# 4_-MECH_BUTTONS.net
KiCad netlist of a schematic drawn in Altium Designer
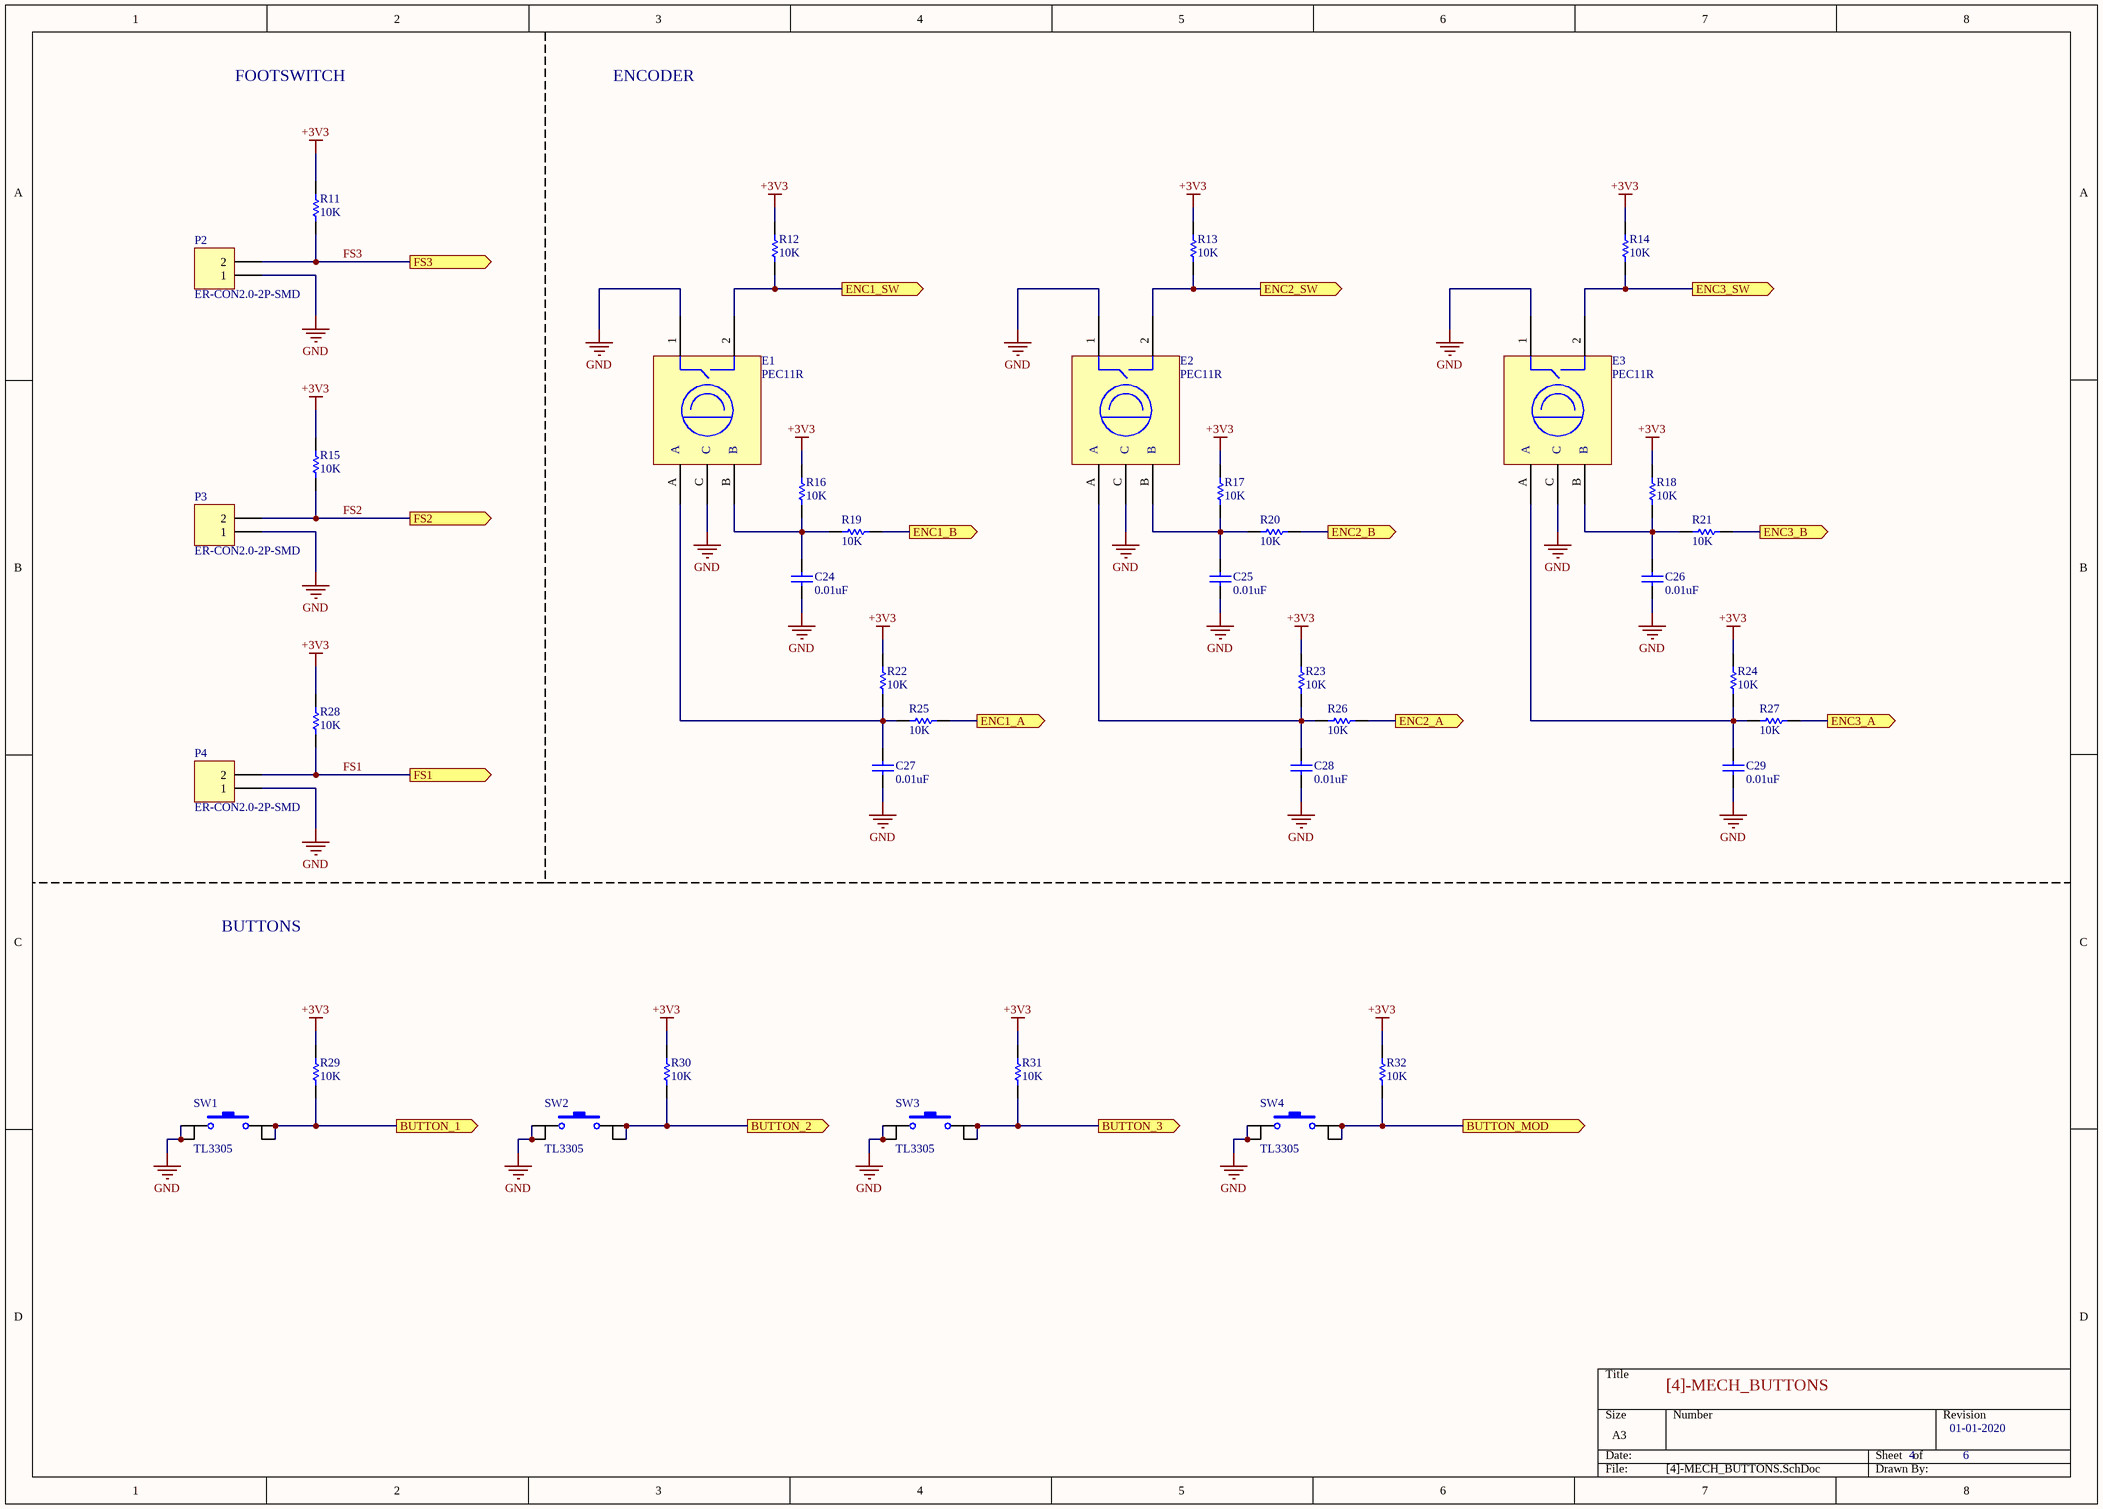
[diagram p0: [4]-MECH_BUTTONS.SchDoc]

(export (version "E")
  (design (tool "Eeschema 10.0.6"))
  (components
    (comp (ref "C24")
      (value "0.01uF")
      (footprint "CAPC1608N")
      (description "CAP CER 10000PF 50V X7R 0603")
      (fields (field (name "TOLERANCE") "10%") (field (name "VOLTAGE") "50V"))
      (libsource (lib "bitsnio") (part "06035C-103KAT2A"))
    )
    (comp (ref "C25")
      (value "0.01uF")
      (footprint "CAPC1608N")
      (description "CAP CER 10000PF 50V X7R 0603")
      (fields (field (name "TOLERANCE") "10%") (field (name "VOLTAGE") "50V"))
      (libsource (lib "bitsnio") (part "06035C-103KAT2A"))
    )
    (comp (ref "C26")
      (value "0.01uF")
      (footprint "CAPC1608N")
      (description "CAP CER 10000PF 50V X7R 0603")
      (fields (field (name "TOLERANCE") "10%") (field (name "VOLTAGE") "50V"))
      (libsource (lib "bitsnio") (part "06035C-103KAT2A"))
    )
    (comp (ref "C27")
      (value "0.01uF")
      (footprint "CAPC1608N")
      (description "CAP CER 10000PF 50V X7R 0603")
      (fields (field (name "TOLERANCE") "10%") (field (name "VOLTAGE") "50V"))
      (libsource (lib "bitsnio") (part "06035C-103KAT2A"))
    )
    (comp (ref "C28")
      (value "0.01uF")
      (footprint "CAPC1608N")
      (description "CAP CER 10000PF 50V X7R 0603")
      (fields (field (name "TOLERANCE") "10%") (field (name "VOLTAGE") "50V"))
      (libsource (lib "bitsnio") (part "06035C-103KAT2A"))
    )
    (comp (ref "C29")
      (value "0.01uF")
      (footprint "CAPC1608N")
      (description "CAP CER 10000PF 50V X7R 0603")
      (fields (field (name "TOLERANCE") "10%") (field (name "VOLTAGE") "50V"))
      (libsource (lib "bitsnio") (part "06035C-103KAT2A"))
    )
    (comp (ref "E1")
      (value "PEC11R")
      (footprint "PEC11R")
      (description "ENCODER ROTARY 15MM SHAFT")
      (libsource (lib "bitsnio") (part "PEC11R-4215F-S0024"))
    )
    (comp (ref "E2")
      (value "PEC11R")
      (footprint "PEC11R")
      (description "ENCODER ROTARY 15MM SHAFT")
      (libsource (lib "bitsnio") (part "PEC11R-4215F-S0024"))
    )
    (comp (ref "E3")
      (value "PEC11R")
      (footprint "PEC11R")
      (description "ENCODER ROTARY 15MM SHAFT")
      (libsource (lib "bitsnio") (part "PEC11R-4215F-S0024"))
    )
    (comp (ref "P2")
      (value "ER-CON2.0-2P-SMD")
      (footprint "ER-CON2.0-2P-SMD")
      (description "CONN 2 POS SMD 2MM PITCH")
      (libsource (lib "bitsnio") (part "ER-CON2.0-2P-SMD"))
    )
    (comp (ref "P3")
      (value "ER-CON2.0-2P-SMD")
      (footprint "ER-CON2.0-2P-SMD")
      (description "CONN 2 POS SMD 2MM PITCH")
      (libsource (lib "bitsnio") (part "ER-CON2.0-2P-SMD"))
    )
    (comp (ref "P4")
      (value "ER-CON2.0-2P-SMD")
      (footprint "ER-CON2.0-2P-SMD")
      (description "CONN 2 POS SMD 2MM PITCH")
      (libsource (lib "bitsnio") (part "ER-CON2.0-2P-SMD"))
    )
    (comp (ref "R11")
      (value "10K")
      (footprint "RESC1608N")
      (description "RES SMD 10K OHM 5% 1/10W 0603")
      (fields (field (name "TOLERANCE") "5%"))
      (libsource (lib "bitsnio") (part "AC0603JR-0710KL"))
    )
    (comp (ref "R12")
      (value "10K")
      (footprint "RESC1608N")
      (description "RES SMD 10K OHM 5% 1/10W 0603")
      (fields (field (name "TOLERANCE") "5%"))
      (libsource (lib "bitsnio") (part "AC0603JR-0710KL"))
    )
    (comp (ref "R13")
      (value "10K")
      (footprint "RESC1608N")
      (description "RES SMD 10K OHM 5% 1/10W 0603")
      (fields (field (name "TOLERANCE") "5%"))
      (libsource (lib "bitsnio") (part "AC0603JR-0710KL"))
    )
    (comp (ref "R14")
      (value "10K")
      (footprint "RESC1608N")
      (description "RES SMD 10K OHM 5% 1/10W 0603")
      (fields (field (name "TOLERANCE") "5%"))
      (libsource (lib "bitsnio") (part "AC0603JR-0710KL"))
    )
    (comp (ref "R15")
      (value "10K")
      (footprint "RESC1608N")
      (description "RES SMD 10K OHM 5% 1/10W 0603")
      (fields (field (name "TOLERANCE") "5%"))
      (libsource (lib "bitsnio") (part "AC0603JR-0710KL"))
    )
    (comp (ref "R16")
      (value "10K")
      (footprint "RESC1608N")
      (description "RES SMD 10K OHM 5% 1/10W 0603")
      (fields (field (name "TOLERANCE") "5%"))
      (libsource (lib "bitsnio") (part "AC0603JR-0710KL"))
    )
    (comp (ref "R17")
      (value "10K")
      (footprint "RESC1608N")
      (description "RES SMD 10K OHM 5% 1/10W 0603")
      (fields (field (name "TOLERANCE") "5%"))
      (libsource (lib "bitsnio") (part "AC0603JR-0710KL"))
    )
    (comp (ref "R18")
      (value "10K")
      (footprint "RESC1608N")
      (description "RES SMD 10K OHM 5% 1/10W 0603")
      (fields (field (name "TOLERANCE") "5%"))
      (libsource (lib "bitsnio") (part "AC0603JR-0710KL"))
    )
    (comp (ref "R19")
      (value "10K")
      (footprint "RESC1608N")
      (description "RES SMD 10K OHM 5% 1/10W 0603")
      (fields (field (name "TOLERANCE") "5%"))
      (libsource (lib "bitsnio") (part "AC0603JR-0710KL"))
    )
    (comp (ref "R20")
      (value "10K")
      (footprint "RESC1608N")
      (description "RES SMD 10K OHM 5% 1/10W 0603")
      (fields (field (name "TOLERANCE") "5%"))
      (libsource (lib "bitsnio") (part "AC0603JR-0710KL"))
    )
    (comp (ref "R21")
      (value "10K")
      (footprint "RESC1608N")
      (description "RES SMD 10K OHM 5% 1/10W 0603")
      (fields (field (name "TOLERANCE") "5%"))
      (libsource (lib "bitsnio") (part "AC0603JR-0710KL"))
    )
    (comp (ref "R22")
      (value "10K")
      (footprint "RESC1608N")
      (description "RES SMD 10K OHM 5% 1/10W 0603")
      (fields (field (name "TOLERANCE") "5%"))
      (libsource (lib "bitsnio") (part "AC0603JR-0710KL"))
    )
    (comp (ref "R23")
      (value "10K")
      (footprint "RESC1608N")
      (description "RES SMD 10K OHM 5% 1/10W 0603")
      (fields (field (name "TOLERANCE") "5%"))
      (libsource (lib "bitsnio") (part "AC0603JR-0710KL"))
    )
    (comp (ref "R24")
      (value "10K")
      (footprint "RESC1608N")
      (description "RES SMD 10K OHM 5% 1/10W 0603")
      (fields (field (name "TOLERANCE") "5%"))
      (libsource (lib "bitsnio") (part "AC0603JR-0710KL"))
    )
    (comp (ref "R25")
      (value "10K")
      (footprint "RESC1608N")
      (description "RES SMD 10K OHM 5% 1/10W 0603")
      (fields (field (name "TOLERANCE") "5%"))
      (libsource (lib "bitsnio") (part "AC0603JR-0710KL"))
    )
    (comp (ref "R26")
      (value "10K")
      (footprint "RESC1608N")
      (description "RES SMD 10K OHM 5% 1/10W 0603")
      (fields (field (name "TOLERANCE") "5%"))
      (libsource (lib "bitsnio") (part "AC0603JR-0710KL"))
    )
    (comp (ref "R27")
      (value "10K")
      (footprint "RESC1608N")
      (description "RES SMD 10K OHM 5% 1/10W 0603")
      (fields (field (name "TOLERANCE") "5%"))
      (libsource (lib "bitsnio") (part "AC0603JR-0710KL"))
    )
    (comp (ref "R28")
      (value "10K")
      (footprint "RESC1608N")
      (description "RES SMD 10K OHM 5% 1/10W 0603")
      (fields (field (name "TOLERANCE") "5%"))
      (libsource (lib "bitsnio") (part "AC0603JR-0710KL"))
    )
    (comp (ref "R29")
      (value "10K")
      (footprint "RESC1608N")
      (description "RES SMD 10K OHM 5% 1/10W 0603")
      (fields (field (name "TOLERANCE") "5%"))
      (libsource (lib "bitsnio") (part "AC0603JR-0710KL"))
    )
    (comp (ref "R30")
      (value "10K")
      (footprint "RESC1608N")
      (description "RES SMD 10K OHM 5% 1/10W 0603")
      (fields (field (name "TOLERANCE") "5%"))
      (libsource (lib "bitsnio") (part "AC0603JR-0710KL"))
    )
    (comp (ref "R31")
      (value "10K")
      (footprint "RESC1608N")
      (description "RES SMD 10K OHM 5% 1/10W 0603")
      (fields (field (name "TOLERANCE") "5%"))
      (libsource (lib "bitsnio") (part "AC0603JR-0710KL"))
    )
    (comp (ref "R32")
      (value "10K")
      (footprint "RESC1608N")
      (description "RES SMD 10K OHM 5% 1/10W 0603")
      (fields (field (name "TOLERANCE") "5%"))
      (libsource (lib "bitsnio") (part "AC0603JR-0710KL"))
    )
    (comp (ref "SW1")
      (value "TL3305")
      (footprint "TL3305")
      (description "SWITCH TACTILE SPST-NO 50MA 12V")
      (libsource (lib "bitsnio") (part "TL3305AF160QG"))
    )
    (comp (ref "SW2")
      (value "TL3305")
      (footprint "TL3305")
      (description "SWITCH TACTILE SPST-NO 50MA 12V")
      (libsource (lib "bitsnio") (part "TL3305AF160QG"))
    )
    (comp (ref "SW3")
      (value "TL3305")
      (footprint "TL3305")
      (description "SWITCH TACTILE SPST-NO 50MA 12V")
      (libsource (lib "bitsnio") (part "TL3305AF160QG"))
    )
    (comp (ref "SW4")
      (value "TL3305")
      (footprint "TL3305")
      (description "SWITCH TACTILE SPST-NO 50MA 12V")
      (libsource (lib "bitsnio") (part "TL3305AF160QG"))
    )
  )
  (nets
    (net (code "1") (name "+3V3") (class "Default")
      (node (ref "R11") (pin "1") (pinfunction "1_1") (pintype "passive"))
      (node (ref "R12") (pin "2") (pinfunction "2_2") (pintype "passive"))
      (node (ref "R13") (pin "2") (pinfunction "2_2") (pintype "passive"))
      (node (ref "R14") (pin "2") (pinfunction "2_2") (pintype "passive"))
      (node (ref "R15") (pin "1") (pinfunction "1_1") (pintype "passive"))
      (node (ref "R16") (pin "2") (pinfunction "2_2") (pintype "passive"))
      (node (ref "R17") (pin "2") (pinfunction "2_2") (pintype "passive"))
      (node (ref "R18") (pin "2") (pinfunction "2_2") (pintype "passive"))
      (node (ref "R22") (pin "2") (pinfunction "2_2") (pintype "passive"))
      (node (ref "R23") (pin "2") (pinfunction "2_2") (pintype "passive"))
      (node (ref "R24") (pin "2") (pinfunction "2_2") (pintype "passive"))
      (node (ref "R28") (pin "1") (pinfunction "1_1") (pintype "passive"))
      (node (ref "R29") (pin "2") (pinfunction "2_2") (pintype "passive"))
      (node (ref "R30") (pin "2") (pinfunction "2_2") (pintype "passive"))
      (node (ref "R31") (pin "2") (pinfunction "2_2") (pintype "passive"))
      (node (ref "R32") (pin "2") (pinfunction "2_2") (pintype "passive"))
    )
    (net (code "2") (name "/BUTTON_1") (class "Default")
      (node (ref "R29") (pin "1") (pinfunction "1_1") (pintype "passive"))
      (node (ref "SW1") (pin "3") (pinfunction "3_3") (pintype "passive"))
      (node (ref "SW1") (pin "4") (pinfunction "4_4") (pintype "passive"))
    )
    (net (code "3") (name "/BUTTON_2") (class "Default")
      (node (ref "R30") (pin "1") (pinfunction "1_1") (pintype "passive"))
      (node (ref "SW2") (pin "3") (pinfunction "3_3") (pintype "passive"))
      (node (ref "SW2") (pin "4") (pinfunction "4_4") (pintype "passive"))
    )
    (net (code "4") (name "/BUTTON_3") (class "Default")
      (node (ref "R31") (pin "1") (pinfunction "1_1") (pintype "passive"))
      (node (ref "SW3") (pin "3") (pinfunction "3_3") (pintype "passive"))
      (node (ref "SW3") (pin "4") (pinfunction "4_4") (pintype "passive"))
    )
    (net (code "5") (name "/BUTTON_MOD") (class "Default")
      (node (ref "R32") (pin "1") (pinfunction "1_1") (pintype "passive"))
      (node (ref "SW4") (pin "3") (pinfunction "3_3") (pintype "passive"))
      (node (ref "SW4") (pin "4") (pinfunction "4_4") (pintype "passive"))
    )
    (net (code "6") (name "/ENC1_A") (class "Default")
      (node (ref "R25") (pin "1") (pinfunction "1_1") (pintype "passive"))
    )
    (net (code "7") (name "/ENC1_B") (class "Default")
      (node (ref "R19") (pin "1") (pinfunction "1_1") (pintype "passive"))
    )
    (net (code "8") (name "/ENC1_SW") (class "Default")
      (node (ref "E1") (pin "2") (pinfunction "2_2") (pintype "passive"))
      (node (ref "R12") (pin "1") (pinfunction "1_1") (pintype "passive"))
    )
    (net (code "9") (name "/ENC2_A") (class "Default")
      (node (ref "R26") (pin "1") (pinfunction "1_1") (pintype "passive"))
    )
    (net (code "10") (name "/ENC2_B") (class "Default")
      (node (ref "R20") (pin "1") (pinfunction "1_1") (pintype "passive"))
    )
    (net (code "11") (name "/ENC2_SW") (class "Default")
      (node (ref "E2") (pin "2") (pinfunction "2_2") (pintype "passive"))
      (node (ref "R13") (pin "1") (pinfunction "1_1") (pintype "passive"))
    )
    (net (code "12") (name "/ENC3_A") (class "Default")
      (node (ref "R27") (pin "1") (pinfunction "1_1") (pintype "passive"))
    )
    (net (code "13") (name "/ENC3_B") (class "Default")
      (node (ref "R21") (pin "1") (pinfunction "1_1") (pintype "passive"))
    )
    (net (code "14") (name "/ENC3_SW") (class "Default")
      (node (ref "E3") (pin "2") (pinfunction "2_2") (pintype "passive"))
      (node (ref "R14") (pin "1") (pinfunction "1_1") (pintype "passive"))
    )
    (net (code "15") (name "/FS1") (class "Default")
      (node (ref "P4") (pin "2") (pinfunction "2_2") (pintype "passive"))
      (node (ref "R28") (pin "2") (pinfunction "2_2") (pintype "passive"))
    )
    (net (code "16") (name "/FS2") (class "Default")
      (node (ref "P3") (pin "2") (pinfunction "2_2") (pintype "passive"))
      (node (ref "R15") (pin "2") (pinfunction "2_2") (pintype "passive"))
    )
    (net (code "17") (name "/FS3") (class "Default")
      (node (ref "P2") (pin "2") (pinfunction "2_2") (pintype "passive"))
      (node (ref "R11") (pin "2") (pinfunction "2_2") (pintype "passive"))
    )
    (net (code "18") (name "GND") (class "Default")
      (node (ref "C24") (pin "1") (pinfunction "1_1") (pintype "passive"))
      (node (ref "C25") (pin "1") (pinfunction "1_1") (pintype "passive"))
      (node (ref "C26") (pin "1") (pinfunction "1_1") (pintype "passive"))
      (node (ref "C27") (pin "1") (pinfunction "1_1") (pintype "passive"))
      (node (ref "C28") (pin "1") (pinfunction "1_1") (pintype "passive"))
      (node (ref "C29") (pin "1") (pinfunction "1_1") (pintype "passive"))
      (node (ref "E1") (pin "1") (pinfunction "1_1") (pintype "passive"))
      (node (ref "E1") (pin "C") (pinfunction "C_C") (pintype "passive"))
      (node (ref "E2") (pin "1") (pinfunction "1_1") (pintype "passive"))
      (node (ref "E2") (pin "C") (pinfunction "C_C") (pintype "passive"))
      (node (ref "E3") (pin "1") (pinfunction "1_1") (pintype "passive"))
      (node (ref "E3") (pin "C") (pinfunction "C_C") (pintype "passive"))
      (node (ref "P2") (pin "1") (pinfunction "1_1") (pintype "passive"))
      (node (ref "P3") (pin "1") (pinfunction "1_1") (pintype "passive"))
      (node (ref "P4") (pin "1") (pinfunction "1_1") (pintype "passive"))
      (node (ref "SW1") (pin "1") (pinfunction "1_1") (pintype "passive"))
      (node (ref "SW1") (pin "2") (pinfunction "2_2") (pintype "passive"))
      (node (ref "SW2") (pin "1") (pinfunction "1_1") (pintype "passive"))
      (node (ref "SW2") (pin "2") (pinfunction "2_2") (pintype "passive"))
      (node (ref "SW3") (pin "1") (pinfunction "1_1") (pintype "passive"))
      (node (ref "SW3") (pin "2") (pinfunction "2_2") (pintype "passive"))
      (node (ref "SW4") (pin "1") (pinfunction "1_1") (pintype "passive"))
      (node (ref "SW4") (pin "2") (pinfunction "2_2") (pintype "passive"))
    )
    (net (code "19") (name "Net-(C24-Pad2)") (class "Default")
      (node (ref "C24") (pin "2") (pinfunction "2_2") (pintype "passive"))
      (node (ref "E1") (pin "B") (pinfunction "B_B") (pintype "passive"))
      (node (ref "R16") (pin "1") (pinfunction "1_1") (pintype "passive"))
      (node (ref "R19") (pin "2") (pinfunction "2_2") (pintype "passive"))
    )
    (net (code "20") (name "Net-(C25-Pad2)") (class "Default")
      (node (ref "C25") (pin "2") (pinfunction "2_2") (pintype "passive"))
      (node (ref "E2") (pin "B") (pinfunction "B_B") (pintype "passive"))
      (node (ref "R17") (pin "1") (pinfunction "1_1") (pintype "passive"))
      (node (ref "R20") (pin "2") (pinfunction "2_2") (pintype "passive"))
    )
    (net (code "21") (name "Net-(C26-Pad2)") (class "Default")
      (node (ref "C26") (pin "2") (pinfunction "2_2") (pintype "passive"))
      (node (ref "E3") (pin "B") (pinfunction "B_B") (pintype "passive"))
      (node (ref "R18") (pin "1") (pinfunction "1_1") (pintype "passive"))
      (node (ref "R21") (pin "2") (pinfunction "2_2") (pintype "passive"))
    )
    (net (code "22") (name "Net-(C27-Pad2)") (class "Default")
      (node (ref "C27") (pin "2") (pinfunction "2_2") (pintype "passive"))
      (node (ref "E1") (pin "A") (pinfunction "A_A") (pintype "passive"))
      (node (ref "R22") (pin "1") (pinfunction "1_1") (pintype "passive"))
      (node (ref "R25") (pin "2") (pinfunction "2_2") (pintype "passive"))
    )
    (net (code "23") (name "Net-(C28-Pad2)") (class "Default")
      (node (ref "C28") (pin "2") (pinfunction "2_2") (pintype "passive"))
      (node (ref "E2") (pin "A") (pinfunction "A_A") (pintype "passive"))
      (node (ref "R23") (pin "1") (pinfunction "1_1") (pintype "passive"))
      (node (ref "R26") (pin "2") (pinfunction "2_2") (pintype "passive"))
    )
    (net (code "24") (name "Net-(C29-Pad2)") (class "Default")
      (node (ref "C29") (pin "2") (pinfunction "2_2") (pintype "passive"))
      (node (ref "E3") (pin "A") (pinfunction "A_A") (pintype "passive"))
      (node (ref "R24") (pin "1") (pinfunction "1_1") (pintype "passive"))
      (node (ref "R27") (pin "2") (pinfunction "2_2") (pintype "passive"))
    )
  )
)
